# LM74910H_PINOUT.net
KiCad netlist of a schematic drawn in Altium Designer
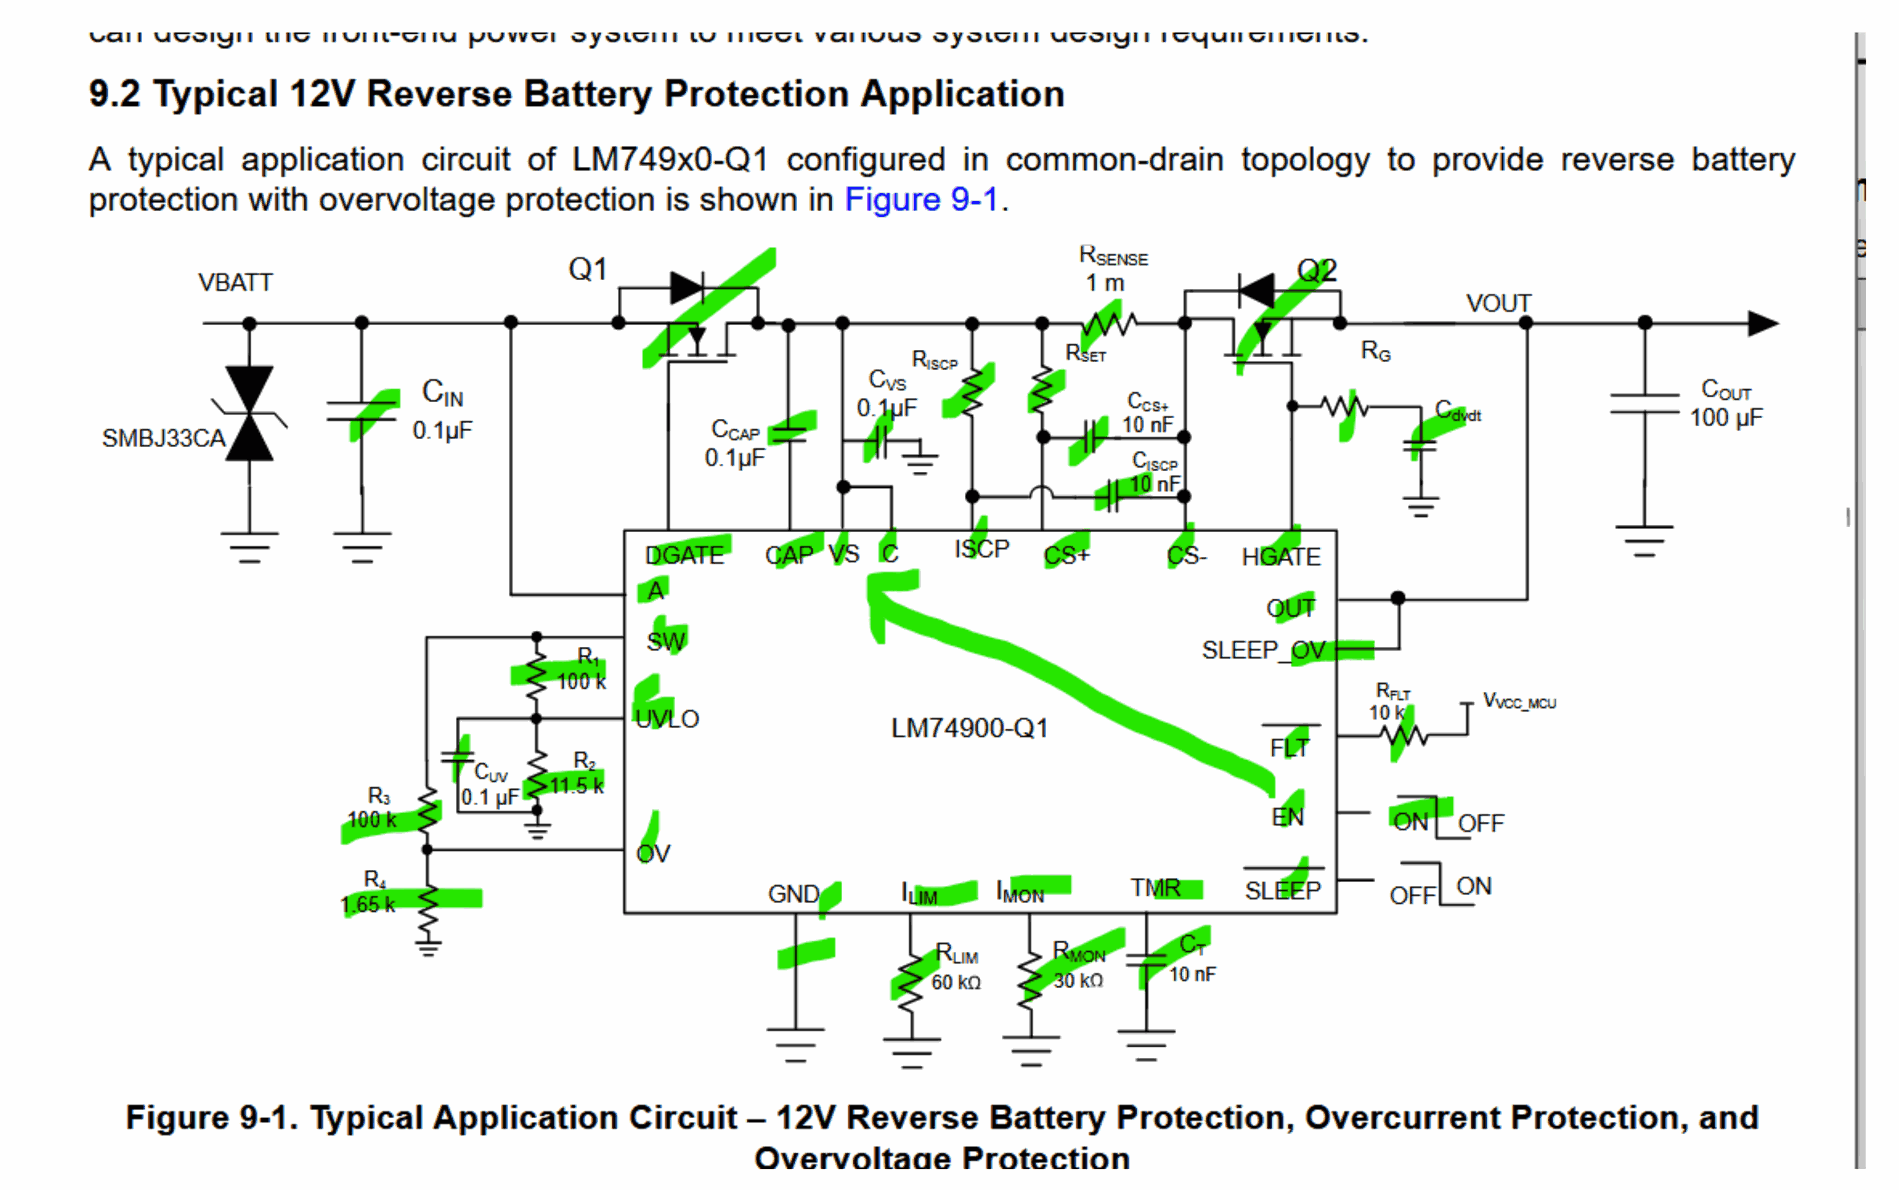
[diagram p0: LM74910H_PINOUT.SchDoc, top]
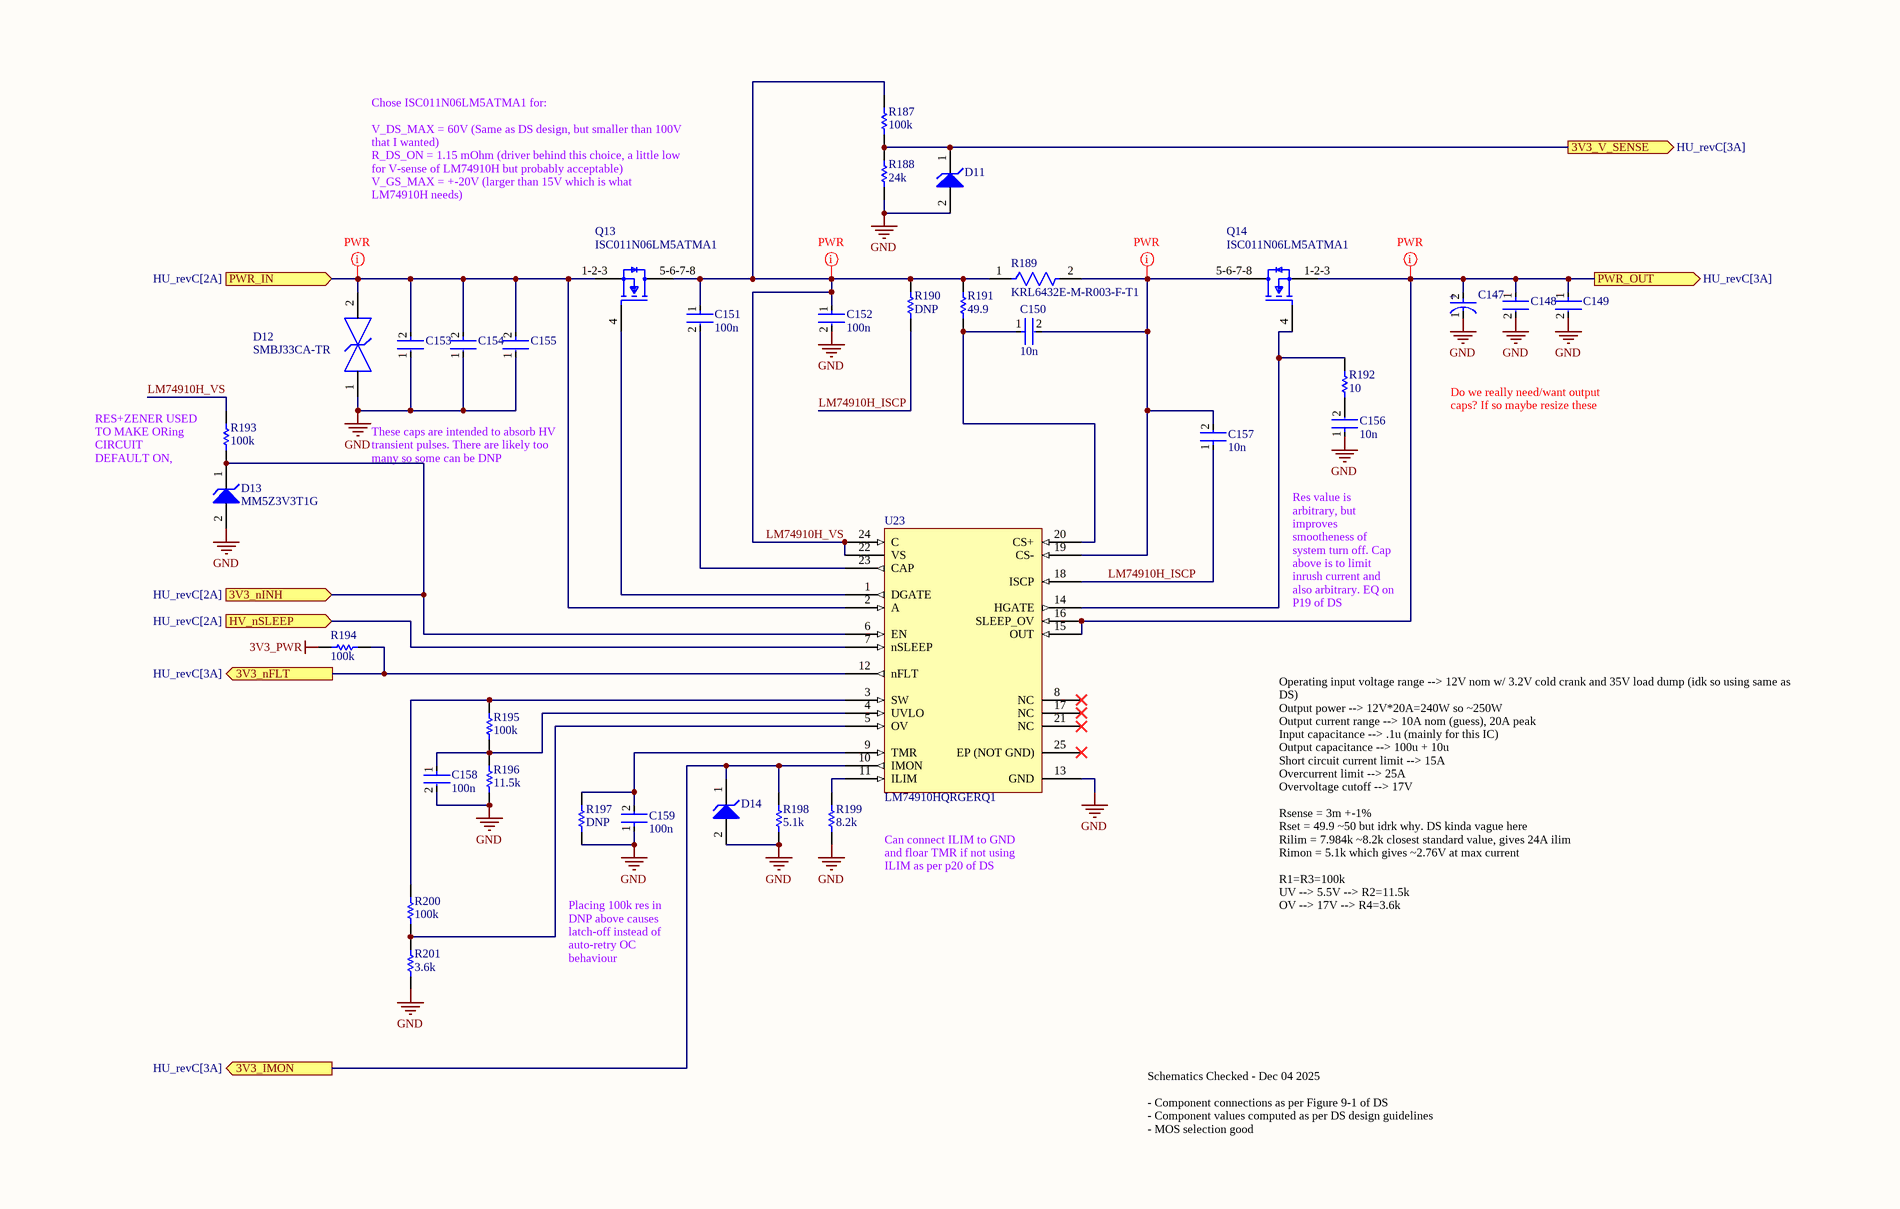
[diagram p1: LM74910H_PINOUT.SchDoc, bottom]

(export (version "E")
  (design (tool "Eeschema 10.0.6"))
  (components
    (comp (ref "C147")
      (value "EEE-FK1H100UR")
      (footprint "FP-FKC-MFG")
      (description "CAP ALUM 10UF 20% 50V SMD")
      (fields (field (name "TOLERANCE") "20%") (field (name "VOLTAGE") "50V"))
      (libsource (lib "Altium Content Vault") (part "a00bbbee19879c290e62620ae7e47b1"))
    )
    (comp (ref "C148")
      (value "12103D106KAT2A")
      (footprint "FP-1210-L_3_3_0_4-W_2_5_0-MFG")
      (description "General Purpose Ceramic Capacitor, 1210, 10uF, 10%, X5R, 15%, 25V")
      (fields (field (name "VOLTAGE") "25V") (field (name "TOLERANCE") "10%"))
      (libsource (lib "Altium Content Vault") (part "b4654b650e69147ec39a6b967a45e02"))
    )
    (comp (ref "C149")
      (value "12103D106KAT2A")
      (footprint "FP-1210-L_3_3_0_4-W_2_5_0-MFG")
      (description "General Purpose Ceramic Capacitor, 1210, 10uF, 10%, X5R, 15%, 25V")
      (fields (field (name "VOLTAGE") "25V") (field (name "TOLERANCE") "10%"))
      (libsource (lib "Altium Content Vault") (part "b4654b650e69147ec39a6b967a45e02"))
    )
    (comp (ref "C150")
      (value "10n")
      (footprint "FP-0402-L_1_0_0_05-W_0_5-IPC_A")
      (description "LARGE PADS, 0402 CAP, CHANGE COMMENT TO MATCH REAL P/N")
      (libsource (lib "Space Concordia") (part "b4654b650e69147ec39a6b967a45e02"))
    )
    (comp (ref "C151")
      (value "100n")
      (footprint "FP-0402-L_1_0_0_05-W_0_5-IPC_A")
      (description "LARGE PADS, 0402 CAP, CHANGE COMMENT TO MATCH REAL P/N")
      (libsource (lib "Space Concordia") (part "b4654b650e69147ec39a6b967a45e02"))
    )
    (comp (ref "C152")
      (value "100n")
      (footprint "FP-0402-L_1_0_0_05-W_0_5-IPC_A")
      (description "LARGE PADS, 0402 CAP, CHANGE COMMENT TO MATCH REAL P/N")
      (libsource (lib "Space Concordia") (part "b4654b650e69147ec39a6b967a45e02"))
    )
    (comp (ref "C153")
      (value "AC1210KKX7R0BB104")
      (footprint "FP-AC1210-0_85-MFG")
      (description "CAP CER 0.1UF 100V X7R 1210")
      (fields (field (name "MANUFACTURER") "Yageo") (field (name "TOLERANCE") "0.1"))
      (libsource (lib "Altium Content Vault") (part "236180d848d6139a670b325ea6854c9"))
    )
    (comp (ref "C154")
      (value "AC1210KKX7R0BB104")
      (footprint "FP-AC1210-0_85-MFG")
      (description "CAP CER 0.1UF 100V X7R 1210")
      (fields (field (name "MANUFACTURER") "Yageo") (field (name "TOLERANCE") "0.1"))
      (libsource (lib "Altium Content Vault") (part "236180d848d6139a670b325ea6854c9"))
    )
    (comp (ref "C155")
      (value "AC1210KKX7R0BB104")
      (footprint "FP-AC1210-0_85-MFG")
      (description "CAP CER 0.1UF 100V X7R 1210")
      (fields (field (name "MANUFACTURER") "Yageo") (field (name "TOLERANCE") "0.1"))
      (libsource (lib "Altium Content Vault") (part "236180d848d6139a670b325ea6854c9"))
    )
    (comp (ref "C156")
      (value "10n")
      (footprint "FP-0402-L_1_0_0_05-W_0_5-IPC_A")
      (description "LARGE PADS, 0402 CAP, CHANGE COMMENT TO MATCH REAL P/N")
      (libsource (lib "Space Concordia") (part "b4654b650e69147ec39a6b967a45e02"))
    )
    (comp (ref "C157")
      (value "10n")
      (footprint "FP-0402-L_1_0_0_05-W_0_5-IPC_A")
      (description "LARGE PADS, 0402 CAP, CHANGE COMMENT TO MATCH REAL P/N")
      (libsource (lib "Space Concordia") (part "b4654b650e69147ec39a6b967a45e02"))
    )
    (comp (ref "C158")
      (value "100n")
      (footprint "FP-0402-L_1_0_0_05-W_0_5-IPC_A")
      (description "LARGE PADS, 0402 CAP, CHANGE COMMENT TO MATCH REAL P/N")
      (libsource (lib "Space Concordia") (part "b4654b650e69147ec39a6b967a45e02"))
    )
    (comp (ref "C159")
      (value "100n")
      (footprint "FP-0402-L_1_0_0_05-W_0_5-IPC_A")
      (description "LARGE PADS, 0402 CAP, CHANGE COMMENT TO MATCH REAL P/N")
      (libsource (lib "Space Concordia") (part "b4654b650e69147ec39a6b967a45e02"))
    )
    (comp (ref "D11")
      (value "DNP/MM5Z3V3T1G")
      (footprint "ONSC-SOD-523-2-502-01_V")
      (description "Zener Voltage Regulator, 500 mW, 2-Pin SOD-523, Pb-Free, Tape and Reel")
      (fields (field (name "MANUFACTURER") "On Semiconductor") (field (name "PARTNUMBER") "MM5Z3V3T1G"))
      (libsource (lib "Altium Content Vault") (part "ONSC-K1A2-2"))
    )
    (comp (ref "D12")
      (value "SMBJ33CA-TR")
      (footprint "FP-SMB-CA-MFG")
      (description "TVS DIODE 33V 69.7V SMB")
      (fields
        (field (name "OCTOPART") "https://octopart.com/smbj33ca-tr-stmicroelectronics-347069")
        (field (name "MANUFACTURER") "STMicroelectronics")
      )
      (libsource (lib "Altium Content Vault") (part "11bd9d59d340f0612179daf16ad9b72"))
    )
    (comp (ref "D13")
      (value "MM5Z3V3T1G")
      (footprint "ONSC-SOD-523-2-502-01_V")
      (description "Zener Voltage Regulator, 500 mW, 2-Pin SOD-523, Pb-Free, Tape and Reel")
      (fields (field (name "MANUFACTURER") "On Semiconductor"))
      (libsource (lib "Altium Content Vault") (part "ONSC-K1A2-2"))
    )
    (comp (ref "D14")
      (value "DNP/MM5Z3V3T1G")
      (footprint "ONSC-SOD-523-2-502-01_V")
      (description "Zener Voltage Regulator, 500 mW, 2-Pin SOD-523, Pb-Free, Tape and Reel")
      (fields (field (name "MANUFACTURER") "On Semiconductor") (field (name "PARTNUMBER") "MM5Z3V3T1G"))
      (libsource (lib "Altium Content Vault") (part "ONSC-K1A2-2"))
    )
    (comp (ref "Q13")
      (value "ISC011N06LM5ATMA1")
      (footprint "FP-PG-TDSON-8-MFG")
      (description "TRENCH 40<-<100V PG-TDSON-8")
      (libsource (lib "Altium Content Vault") (part "3085234d4498bcd04bc7e5400bb7c96"))
    )
    (comp (ref "Q14")
      (value "ISC011N06LM5ATMA1")
      (footprint "FP-PG-TDSON-8-MFG")
      (description "TRENCH 40<-<100V PG-TDSON-8")
      (libsource (lib "Altium Content Vault") (part "3085234d4498bcd04bc7e5400bb7c96"))
    )
    (comp (ref "R187")
      (value "100k")
      (footprint "R0603B")
      (description "Resistor")
      (libsource (lib "Space Concordia") (part "Resistor"))
    )
    (comp (ref "R188")
      (value "24k")
      (footprint "R0603B")
      (description "Resistor")
      (libsource (lib "Space Concordia") (part "Resistor"))
    )
    (comp (ref "R189")
      (value "KRL6432E-M-R003-F-T1")
      (footprint "FP-KRL6432E-MFG")
      (description "KRL6432E-M-R003-F-T1 Metal Foil Low Resistance Chip Resistor (long-side terminal), 2512, RoHS")
      (fields (field (name "TOLERANCE") "1%"))
      (libsource (lib "Altium Content Vault") (part "1029c3af85768c4190bb7ad29bc67b5"))
    )
    (comp (ref "R190")
      (value "DNP")
      (footprint "R0603B")
      (description "Resistor")
      (libsource (lib "Space Concordia") (part "Resistor"))
    )
    (comp (ref "R191")
      (value "49.9")
      (footprint "R0603B")
      (description "Resistor")
      (libsource (lib "Space Concordia") (part "Resistor"))
    )
    (comp (ref "R192")
      (value "10")
      (footprint "R0603B")
      (description "Resistor")
      (libsource (lib "Space Concordia") (part "Resistor"))
    )
    (comp (ref "R193")
      (value "100k")
      (footprint "R0603B")
      (description "Resistor")
      (libsource (lib "Space Concordia") (part "Resistor"))
    )
    (comp (ref "R194")
      (value "100k")
      (footprint "R0603B")
      (description "Resistor")
      (libsource (lib "Space Concordia") (part "Resistor"))
    )
    (comp (ref "R195")
      (value "100k")
      (footprint "R0603B")
      (description "Resistor")
      (libsource (lib "Space Concordia") (part "Resistor"))
    )
    (comp (ref "R196")
      (value "11.5k")
      (footprint "R0603B")
      (description "Resistor")
      (libsource (lib "Space Concordia") (part "Resistor"))
    )
    (comp (ref "R197")
      (value "DNP")
      (footprint "R0603B")
      (description "Resistor")
      (libsource (lib "Space Concordia") (part "Resistor"))
    )
    (comp (ref "R198")
      (value "5.1k")
      (footprint "R0603B")
      (description "Resistor")
      (libsource (lib "Space Concordia") (part "Resistor"))
    )
    (comp (ref "R199")
      (value "8.2k")
      (footprint "R0603B")
      (description "Resistor")
      (libsource (lib "Space Concordia") (part "Resistor"))
    )
    (comp (ref "R200")
      (value "100k")
      (footprint "R0603B")
      (description "Resistor")
      (libsource (lib "Space Concordia") (part "Resistor"))
    )
    (comp (ref "R201")
      (value "3.6k")
      (footprint "R0603B")
      (description "Resistor")
      (libsource (lib "Space Concordia") (part "Resistor"))
    )
    (comp (ref "U23")
      (value "LM74910HQRGERQ1")
      (footprint "QFN50P400X400X100_HS-25N")
      (libsource (lib "Space Concordia") (part "LM74910HQRGERQ1"))
    )
  )
  (nets
    (net (code "1") (name "/3V3_IMON") (class "Default")
      (node (ref "D14") (pin "1") (pinfunction "K_1") (pintype "passive"))
      (node (ref "R198") (pin "2") (pinfunction "2_2") (pintype "passive"))
      (node (ref "U23") (pin "10") (pinfunction "IMON_10") (pintype "output"))
    )
    (net (code "2") (name "/3V3_V_SENSE") (class "Default")
      (node (ref "D11") (pin "1") (pinfunction "K_1") (pintype "passive"))
      (node (ref "R187") (pin "1") (pinfunction "1_1") (pintype "passive"))
      (node (ref "R188") (pin "2") (pinfunction "2_2") (pintype "passive"))
    )
    (net (code "3") (name "/3V3_nFLT") (class "Default")
      (node (ref "R194") (pin "1") (pinfunction "1_1") (pintype "passive"))
      (node (ref "U23") (pin "12") (pinfunction "nFLT_12") (pintype "output"))
    )
    (net (code "4") (name "/3V3_nINH") (class "Default")
      (node (ref "D13") (pin "1") (pinfunction "K_1") (pintype "passive"))
      (node (ref "R193") (pin "1") (pinfunction "1_1") (pintype "passive"))
      (node (ref "U23") (pin "6") (pinfunction "EN_6") (pintype "input"))
    )
    (net (code "5") (name "/HV_nSLEEP") (class "Default")
      (node (ref "U23") (pin "7") (pinfunction "nSLEEP_7") (pintype "input"))
    )
    (net (code "6") (name "/LM74910H_ISCP") (class "Default")
      (node (ref "C157") (pin "1") (pinfunction "1_1") (pintype "passive"))
      (node (ref "R190") (pin "1") (pinfunction "1_1") (pintype "passive"))
      (node (ref "U23") (pin "18") (pinfunction "ISCP_18") (pintype "input"))
    )
    (net (code "7") (name "/LM74910H_VS") (class "Default")
      (node (ref "C151") (pin "1") (pinfunction "1_1") (pintype "passive"))
      (node (ref "C152") (pin "1") (pinfunction "1_1") (pintype "passive"))
      (node (ref "Q13") (pin "5-6-7-8") (pinfunction "D_5-6-7-8") (pintype "passive"))
      (node (ref "R187") (pin "2") (pinfunction "2_2") (pintype "passive"))
      (node (ref "R189") (pin "1") (pinfunction "1_1") (pintype "passive"))
      (node (ref "R190") (pin "2") (pinfunction "2_2") (pintype "passive"))
      (node (ref "R191") (pin "2") (pinfunction "2_2") (pintype "passive"))
      (node (ref "R193") (pin "2") (pinfunction "2_2") (pintype "passive"))
      (node (ref "U23") (pin "22") (pinfunction "VS_22") (pintype "power_in"))
      (node (ref "U23") (pin "24") (pinfunction "C_24") (pintype "input"))
    )
    (net (code "8") (name "/PWR_IN") (class "Default")
      (node (ref "C153") (pin "2") (pinfunction "2_2") (pintype "passive"))
      (node (ref "C154") (pin "2") (pinfunction "2_2") (pintype "passive"))
      (node (ref "C155") (pin "2") (pinfunction "2_2") (pintype "passive"))
      (node (ref "D12") (pin "2") (pinfunction "2_2") (pintype "passive"))
      (node (ref "Q13") (pin "1-2-3") (pinfunction "S_1-2-3") (pintype "passive"))
      (node (ref "U23") (pin "2") (pinfunction "A_2") (pintype "input"))
    )
    (net (code "9") (name "/PWR_OUT") (class "Default")
      (node (ref "C147") (pin "2") (pinfunction "A_2") (pintype "passive"))
      (node (ref "C148") (pin "1") (pinfunction "1_1") (pintype "passive"))
      (node (ref "C149") (pin "1") (pinfunction "1_1") (pintype "passive"))
      (node (ref "Q14") (pin "1-2-3") (pinfunction "S_1-2-3") (pintype "passive"))
      (node (ref "U23") (pin "15") (pinfunction "OUT_15") (pintype "input"))
      (node (ref "U23") (pin "16") (pinfunction "SLEEP_OV_16") (pintype "input"))
    )
    (net (code "10") (name "3V3_PWR") (class "Default")
      (node (ref "R194") (pin "2") (pinfunction "2_2") (pintype "passive"))
    )
    (net (code "11") (name "GND") (class "Default")
      (node (ref "C147") (pin "1") (pinfunction "C_1") (pintype "passive"))
      (node (ref "C148") (pin "2") (pinfunction "2_2") (pintype "passive"))
      (node (ref "C149") (pin "2") (pinfunction "2_2") (pintype "passive"))
      (node (ref "C152") (pin "2") (pinfunction "2_2") (pintype "passive"))
      (node (ref "C153") (pin "1") (pinfunction "1_1") (pintype "passive"))
      (node (ref "C154") (pin "1") (pinfunction "1_1") (pintype "passive"))
      (node (ref "C155") (pin "1") (pinfunction "1_1") (pintype "passive"))
      (node (ref "C156") (pin "1") (pinfunction "1_1") (pintype "passive"))
      (node (ref "C158") (pin "2") (pinfunction "2_2") (pintype "passive"))
      (node (ref "C159") (pin "1") (pinfunction "1_1") (pintype "passive"))
      (node (ref "D11") (pin "2") (pinfunction "A_2") (pintype "passive"))
      (node (ref "D12") (pin "1") (pinfunction "1_1") (pintype "passive"))
      (node (ref "D13") (pin "2") (pinfunction "A_2") (pintype "passive"))
      (node (ref "D14") (pin "2") (pinfunction "A_2") (pintype "passive"))
      (node (ref "R188") (pin "1") (pinfunction "1_1") (pintype "passive"))
      (node (ref "R196") (pin "1") (pinfunction "1_1") (pintype "passive"))
      (node (ref "R197") (pin "1") (pinfunction "1_1") (pintype "passive"))
      (node (ref "R198") (pin "1") (pinfunction "1_1") (pintype "passive"))
      (node (ref "R199") (pin "1") (pinfunction "1_1") (pintype "passive"))
      (node (ref "R201") (pin "1") (pinfunction "1_1") (pintype "passive"))
      (node (ref "U23") (pin "13") (pinfunction "GND_13") (pintype "power_in"))
    )
    (net (code "12") (name "Net-(C156-Pad2)") (class "Default")
      (node (ref "C156") (pin "2") (pinfunction "2_2") (pintype "passive"))
      (node (ref "R192") (pin "1") (pinfunction "1_1") (pintype "passive"))
    )
    (net (code "13") (name "Net-(Q13-G)") (class "Default")
      (node (ref "Q13") (pin "4") (pinfunction "G_4") (pintype "passive"))
      (node (ref "U23") (pin "1") (pinfunction "DGATE_1") (pintype "output"))
    )
    (net (code "14") (name "Net-(Q14-D)") (class "Default")
      (node (ref "C150") (pin "2") (pinfunction "2_2") (pintype "passive"))
      (node (ref "C157") (pin "2") (pinfunction "2_2") (pintype "passive"))
      (node (ref "Q14") (pin "5-6-7-8") (pinfunction "D_5-6-7-8") (pintype "passive"))
      (node (ref "R189") (pin "2") (pinfunction "2_2") (pintype "passive"))
      (node (ref "U23") (pin "19") (pinfunction "CS-_19") (pintype "input"))
    )
    (net (code "15") (name "Net-(Q14-G)") (class "Default")
      (node (ref "Q14") (pin "4") (pinfunction "G_4") (pintype "passive"))
      (node (ref "R192") (pin "2") (pinfunction "2_2") (pintype "passive"))
      (node (ref "U23") (pin "14") (pinfunction "HGATE_14") (pintype "output"))
    )
    (net (code "16") (name "Net-(U23-CAP)") (class "Default")
      (node (ref "C151") (pin "2") (pinfunction "2_2") (pintype "passive"))
      (node (ref "U23") (pin "23") (pinfunction "CAP_23") (pintype "output"))
    )
    (net (code "17") (name "Net-(U23-CS+)") (class "Default")
      (node (ref "C150") (pin "1") (pinfunction "1_1") (pintype "passive"))
      (node (ref "R191") (pin "1") (pinfunction "1_1") (pintype "passive"))
      (node (ref "U23") (pin "20") (pinfunction "CS+_20") (pintype "input"))
    )
    (net (code "18") (name "Net-(U23-ILIM)") (class "Default")
      (node (ref "R199") (pin "2") (pinfunction "2_2") (pintype "passive"))
      (node (ref "U23") (pin "11") (pinfunction "ILIM_11") (pintype "input"))
    )
    (net (code "19") (name "Net-(U23-OV)") (class "Default")
      (node (ref "R200") (pin "1") (pinfunction "1_1") (pintype "passive"))
      (node (ref "R201") (pin "2") (pinfunction "2_2") (pintype "passive"))
      (node (ref "U23") (pin "5") (pinfunction "OV_5") (pintype "input"))
    )
    (net (code "20") (name "Net-(U23-SW)") (class "Default")
      (node (ref "R195") (pin "2") (pinfunction "2_2") (pintype "passive"))
      (node (ref "R200") (pin "2") (pinfunction "2_2") (pintype "passive"))
      (node (ref "U23") (pin "3") (pinfunction "SW_3") (pintype "input"))
    )
    (net (code "21") (name "Net-(U23-TMR)") (class "Default")
      (node (ref "C159") (pin "2") (pinfunction "2_2") (pintype "passive"))
      (node (ref "R197") (pin "2") (pinfunction "2_2") (pintype "passive"))
      (node (ref "U23") (pin "9") (pinfunction "TMR_9") (pintype "input"))
    )
    (net (code "22") (name "Net-(U23-UVLO)") (class "Default")
      (node (ref "C158") (pin "1") (pinfunction "1_1") (pintype "passive"))
      (node (ref "R195") (pin "1") (pinfunction "1_1") (pintype "passive"))
      (node (ref "R196") (pin "2") (pinfunction "2_2") (pintype "passive"))
      (node (ref "U23") (pin "4") (pinfunction "UVLO_4") (pintype "input"))
    )
    (net (code "23") (name "unconnected-(U23-EP_(NOT_GND)-Pad25)") (class "Default")
      (node (ref "U23") (pin "25") (pinfunction "EP_(NOT_GND)_25") (pintype "passive+no_connect"))
    )
    (net (code "24") (name "unconnected-(U23-NC-Pad8)") (class "Default")
      (node (ref "U23") (pin "8") (pinfunction "NC_8") (pintype "passive+no_connect"))
    )
    (net (code "25") (name "unconnected-(U23-NC-Pad17)") (class "Default")
      (node (ref "U23") (pin "17") (pinfunction "NC_17") (pintype "passive+no_connect"))
    )
    (net (code "26") (name "unconnected-(U23-NC-Pad21)") (class "Default")
      (node (ref "U23") (pin "21") (pinfunction "NC_21") (pintype "passive+no_connect"))
    )
  )
)
